# BatebitControllerShieldv0_2_0.net
KiCad netlist of a schematic drawn in EAGLE
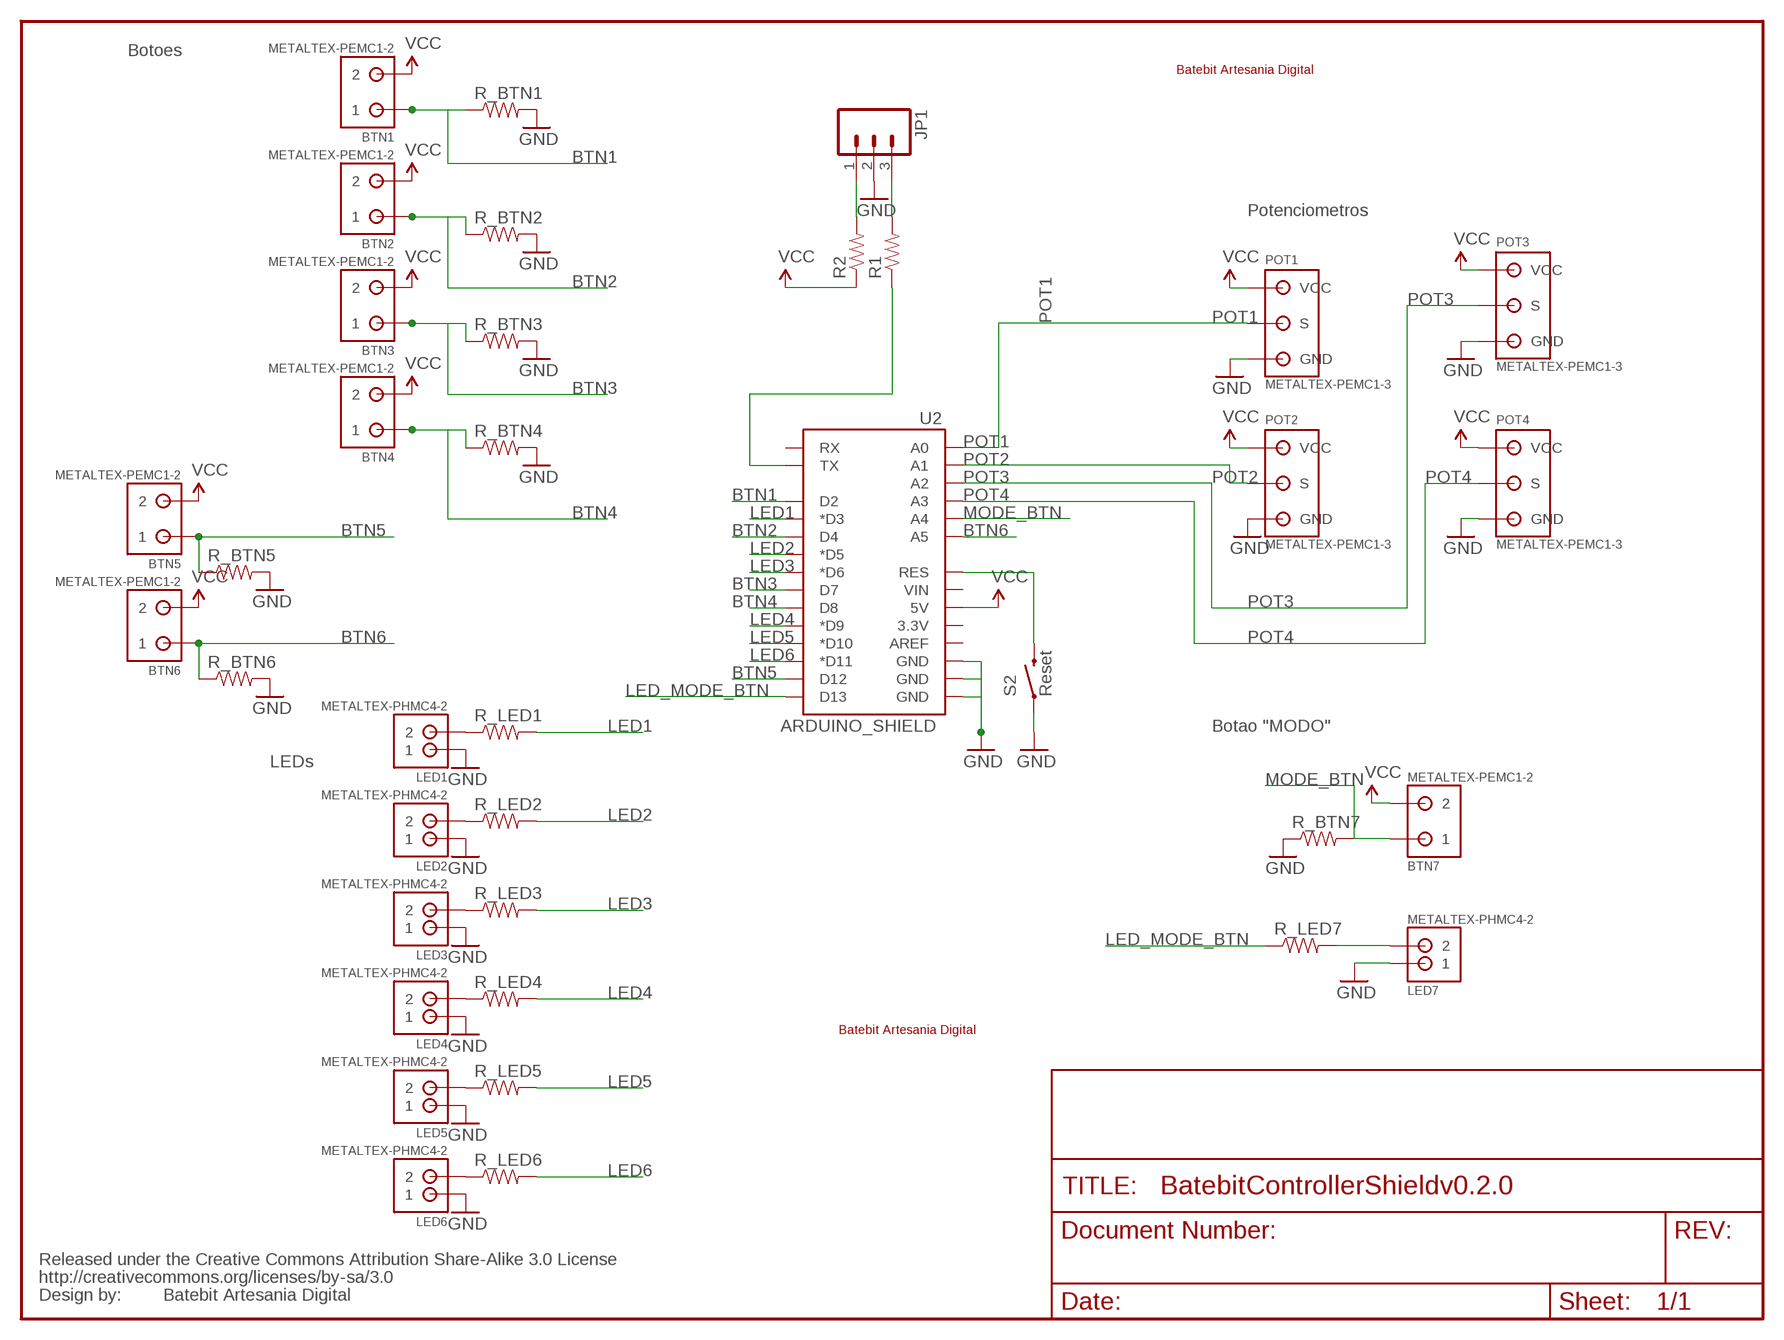
[diagram p0: schematic, sheet 1]

(export (version "E")
  (design (tool "Eeschema 10.0.6"))
  (components
    (comp (ref "BTN1")
      (value "METALTEX-PEMC1-2")
      (footprint "eagle-import:METALTEX-PEMC1-2-PACKAGE-LONG-PAD")
      (libsource (lib "eagle-import") (part "METALTEX-PEMC1-2"))
    )
    (comp (ref "BTN2")
      (value "METALTEX-PEMC1-2")
      (footprint "eagle-import:METALTEX-PEMC1-2-PACKAGE-LONG-PAD")
      (libsource (lib "eagle-import") (part "METALTEX-PEMC1-2"))
    )
    (comp (ref "BTN3")
      (value "METALTEX-PEMC1-2")
      (footprint "eagle-import:METALTEX-PEMC1-2-PACKAGE-LONG-PAD")
      (libsource (lib "eagle-import") (part "METALTEX-PEMC1-2"))
    )
    (comp (ref "BTN4")
      (value "METALTEX-PEMC1-2")
      (footprint "eagle-import:METALTEX-PEMC1-2-PACKAGE-LONG-PAD")
      (libsource (lib "eagle-import") (part "METALTEX-PEMC1-2"))
    )
    (comp (ref "BTN5")
      (value "METALTEX-PEMC1-2")
      (footprint "eagle-import:METALTEX-PEMC1-2-PACKAGE-LONG-PAD")
      (libsource (lib "eagle-import") (part "METALTEX-PEMC1-2"))
    )
    (comp (ref "BTN6")
      (value "METALTEX-PEMC1-2")
      (footprint "eagle-import:METALTEX-PEMC1-2-PACKAGE-LONG-PAD")
      (libsource (lib "eagle-import") (part "METALTEX-PEMC1-2"))
    )
    (comp (ref "BTN7")
      (value "METALTEX-PEMC1-2")
      (footprint "eagle-import:METALTEX-PEMC1-2-PACKAGE-LONG-PAD")
      (libsource (lib "eagle-import") (part "METALTEX-PEMC1-2"))
    )
    (comp (ref "JP1")
      (value "M03LONGPADS")
      (footprint "eagle-import:1X03_LONGPADS")
      (libsource (lib "eagle-import") (part "M03LONGPADS"))
    )
    (comp (ref "LED1")
      (value "METALTEX-PHMC4-2")
      (footprint "eagle-import:METALTEX-PHMC4-2-PACKAGE-LONG-PAD")
      (libsource (lib "eagle-import") (part "METALTEX-PHMC4-2"))
    )
    (comp (ref "LED2")
      (value "METALTEX-PHMC4-2")
      (footprint "eagle-import:METALTEX-PHMC4-2-PACKAGE-LONG-PAD")
      (libsource (lib "eagle-import") (part "METALTEX-PHMC4-2"))
    )
    (comp (ref "LED3")
      (value "METALTEX-PHMC4-2")
      (footprint "eagle-import:METALTEX-PHMC4-2-PACKAGE-LONG-PAD")
      (libsource (lib "eagle-import") (part "METALTEX-PHMC4-2"))
    )
    (comp (ref "LED4")
      (value "METALTEX-PHMC4-2")
      (footprint "eagle-import:METALTEX-PHMC4-2-PACKAGE-LONG-PAD")
      (libsource (lib "eagle-import") (part "METALTEX-PHMC4-2"))
    )
    (comp (ref "LED5")
      (value "METALTEX-PHMC4-2")
      (footprint "eagle-import:METALTEX-PHMC4-2-PACKAGE-LONG-PAD")
      (libsource (lib "eagle-import") (part "METALTEX-PHMC4-2"))
    )
    (comp (ref "LED6")
      (value "METALTEX-PHMC4-2")
      (footprint "eagle-import:METALTEX-PHMC4-2-PACKAGE-LONG-PAD")
      (libsource (lib "eagle-import") (part "METALTEX-PHMC4-2"))
    )
    (comp (ref "LED7")
      (value "METALTEX-PHMC4-2")
      (footprint "eagle-import:METALTEX-PHMC4-2-PACKAGE-LONG-PAD")
      (libsource (lib "eagle-import") (part "METALTEX-PHMC4-2"))
    )
    (comp (ref "POT1")
      (value "METALTEX-PEMC1-3")
      (footprint "eagle-import:METALTEX-PEMC1-3-PACKAGE-LONG-PAD")
      (libsource (lib "eagle-import") (part "METALTEX-PEMC1-3"))
    )
    (comp (ref "POT2")
      (value "METALTEX-PEMC1-3")
      (footprint "eagle-import:METALTEX-PEMC1-3-PACKAGE-LONG-PAD")
      (libsource (lib "eagle-import") (part "METALTEX-PEMC1-3"))
    )
    (comp (ref "POT3")
      (value "METALTEX-PEMC1-3")
      (footprint "eagle-import:METALTEX-PEMC1-3-PACKAGE-LONG-PAD")
      (libsource (lib "eagle-import") (part "METALTEX-PEMC1-3"))
    )
    (comp (ref "POT4")
      (value "METALTEX-PEMC1-3")
      (footprint "eagle-import:METALTEX-PEMC1-3-PACKAGE-LONG-PAD")
      (libsource (lib "eagle-import") (part "METALTEX-PEMC1-3"))
    )
    (comp (ref "R1")
      (value "RESISTOR0805-RES")
      (footprint "eagle-import:0805")
      (libsource (lib "eagle-import") (part "RESISTOR0805-RES"))
    )
    (comp (ref "R2")
      (value "RESISTOR0805-RES")
      (footprint "eagle-import:0805")
      (libsource (lib "eagle-import") (part "RESISTOR0805-RES"))
    )
    (comp (ref "R_BTN1")
      (value "RESISTOR0805-RES")
      (footprint "eagle-import:0805")
      (libsource (lib "eagle-import") (part "RESISTOR0805-RES"))
    )
    (comp (ref "R_BTN2")
      (value "RESISTOR0805-RES")
      (footprint "eagle-import:0805")
      (libsource (lib "eagle-import") (part "RESISTOR0805-RES"))
    )
    (comp (ref "R_BTN3")
      (value "RESISTOR0805-RES")
      (footprint "eagle-import:0805")
      (libsource (lib "eagle-import") (part "RESISTOR0805-RES"))
    )
    (comp (ref "R_BTN4")
      (value "RESISTOR0805-RES")
      (footprint "eagle-import:0805")
      (libsource (lib "eagle-import") (part "RESISTOR0805-RES"))
    )
    (comp (ref "R_BTN5")
      (value "RESISTOR0805-RES")
      (footprint "eagle-import:0805")
      (libsource (lib "eagle-import") (part "RESISTOR0805-RES"))
    )
    (comp (ref "R_BTN6")
      (value "RESISTOR0805-RES")
      (footprint "eagle-import:0805")
      (libsource (lib "eagle-import") (part "RESISTOR0805-RES"))
    )
    (comp (ref "R_BTN7")
      (value "RESISTOR0805-RES")
      (footprint "eagle-import:0805")
      (libsource (lib "eagle-import") (part "RESISTOR0805-RES"))
    )
    (comp (ref "R_LED1")
      (value "RESISTOR0805-RES")
      (footprint "eagle-import:0805")
      (libsource (lib "eagle-import") (part "RESISTOR0805-RES"))
    )
    (comp (ref "R_LED2")
      (value "RESISTOR0805-RES")
      (footprint "eagle-import:0805")
      (libsource (lib "eagle-import") (part "RESISTOR0805-RES"))
    )
    (comp (ref "R_LED3")
      (value "RESISTOR0805-RES")
      (footprint "eagle-import:0805")
      (libsource (lib "eagle-import") (part "RESISTOR0805-RES"))
    )
    (comp (ref "R_LED4")
      (value "RESISTOR0805-RES")
      (footprint "eagle-import:0805")
      (libsource (lib "eagle-import") (part "RESISTOR0805-RES"))
    )
    (comp (ref "R_LED5")
      (value "RESISTOR0805-RES")
      (footprint "eagle-import:0805")
      (libsource (lib "eagle-import") (part "RESISTOR0805-RES"))
    )
    (comp (ref "R_LED6")
      (value "RESISTOR0805-RES")
      (footprint "eagle-import:0805")
      (libsource (lib "eagle-import") (part "RESISTOR0805-RES"))
    )
    (comp (ref "R_LED7")
      (value "RESISTOR0805-RES")
      (footprint "eagle-import:0805")
      (libsource (lib "eagle-import") (part "RESISTOR0805-RES"))
    )
    (comp (ref "S2")
      (value "Reset")
      (footprint "eagle-import:TACTILE_SWITCH_SMD")
      (libsource (lib "eagle-import") (part "SWITCH-MOMENTARY-2SMD"))
    )
    (comp (ref "U$1")
      (value "BATEBITP")
      (footprint "eagle-import:BATEBIT_BRASAO_P")
      (libsource (lib "eagle-import") (part "BATEBITP"))
    )
    (comp (ref "U$2")
      (value "BATEBITMED")
      (footprint "eagle-import:BATEBIT_MED")
      (libsource (lib "eagle-import") (part "BATEBITMED"))
    )
    (comp (ref "U$3")
      (value "CREATIVE_COMMONS")
      (footprint "eagle-import:CREATIVE_COMMONS")
      (libsource (lib "eagle-import") (part "CREATIVE_COMMONS"))
    )
    (comp (ref "U2")
      (value "ARDUINO_SHIELD")
      (footprint "eagle-import:DUEMILANOVE_SHIELD")
      (libsource (lib "eagle-import") (part "ARDUINO_SHIELDLABEL"))
    )
  )
  (nets
    (net (code "1") (name "/BTN1") (class "Default")
      (node (ref "BTN1") (pin "1") (pinfunction "1_1") (pintype "bidirectional"))
      (node (ref "R_BTN1") (pin "1") (pinfunction "1_1") (pintype "passive"))
      (node (ref "U2") (pin "D2") (pinfunction "D2_D2") (pintype "bidirectional"))
    )
    (net (code "2") (name "/BTN2") (class "Default")
      (node (ref "BTN2") (pin "1") (pinfunction "1_1") (pintype "bidirectional"))
      (node (ref "R_BTN2") (pin "1") (pinfunction "1_1") (pintype "passive"))
      (node (ref "U2") (pin "D4") (pinfunction "D4_D4") (pintype "bidirectional"))
    )
    (net (code "3") (name "/BTN3") (class "Default")
      (node (ref "BTN3") (pin "1") (pinfunction "1_1") (pintype "bidirectional"))
      (node (ref "R_BTN3") (pin "1") (pinfunction "1_1") (pintype "passive"))
      (node (ref "U2") (pin "D7") (pinfunction "D7_D7") (pintype "bidirectional"))
    )
    (net (code "4") (name "/BTN4") (class "Default")
      (node (ref "BTN4") (pin "1") (pinfunction "1_1") (pintype "bidirectional"))
      (node (ref "R_BTN4") (pin "1") (pinfunction "1_1") (pintype "passive"))
      (node (ref "U2") (pin "D8") (pinfunction "D8_D8") (pintype "bidirectional"))
    )
    (net (code "5") (name "/BTN5") (class "Default")
      (node (ref "BTN5") (pin "1") (pinfunction "1_1") (pintype "bidirectional"))
      (node (ref "R_BTN5") (pin "1") (pinfunction "1_1") (pintype "passive"))
      (node (ref "U2") (pin "D12") (pinfunction "D12_D12") (pintype "bidirectional"))
    )
    (net (code "6") (name "/BTN6") (class "Default")
      (node (ref "BTN6") (pin "1") (pinfunction "1_1") (pintype "bidirectional"))
      (node (ref "R_BTN6") (pin "1") (pinfunction "1_1") (pintype "passive"))
      (node (ref "U2") (pin "A5") (pinfunction "A5_A5") (pintype "bidirectional"))
    )
    (net (code "7") (name "/LED1") (class "Default")
      (node (ref "R_LED1") (pin "2") (pinfunction "2_2") (pintype "passive"))
      (node (ref "U2") (pin "D3") (pinfunction "*D3_D3") (pintype "bidirectional"))
    )
    (net (code "8") (name "/LED2") (class "Default")
      (node (ref "R_LED2") (pin "2") (pinfunction "2_2") (pintype "passive"))
      (node (ref "U2") (pin "D5") (pinfunction "*D5_D5") (pintype "bidirectional"))
    )
    (net (code "9") (name "/LED3") (class "Default")
      (node (ref "R_LED3") (pin "2") (pinfunction "2_2") (pintype "passive"))
      (node (ref "U2") (pin "D6") (pinfunction "*D6_D6") (pintype "bidirectional"))
    )
    (net (code "10") (name "/LED4") (class "Default")
      (node (ref "R_LED4") (pin "2") (pinfunction "2_2") (pintype "passive"))
      (node (ref "U2") (pin "D9") (pinfunction "*D9_D9") (pintype "bidirectional"))
    )
    (net (code "11") (name "/LED5") (class "Default")
      (node (ref "R_LED5") (pin "2") (pinfunction "2_2") (pintype "passive"))
      (node (ref "U2") (pin "D10") (pinfunction "*D10_D10") (pintype "bidirectional"))
    )
    (net (code "12") (name "/LED6") (class "Default")
      (node (ref "R_LED6") (pin "2") (pinfunction "2_2") (pintype "passive"))
      (node (ref "U2") (pin "D11") (pinfunction "*D11_D11") (pintype "bidirectional"))
    )
    (net (code "13") (name "/LED_MODE_BTN") (class "Default")
      (node (ref "R_LED7") (pin "1") (pinfunction "1_1") (pintype "passive"))
      (node (ref "U2") (pin "D13") (pinfunction "D13_D13") (pintype "bidirectional"))
    )
    (net (code "14") (name "/MODE_BTN") (class "Default")
      (node (ref "BTN7") (pin "1") (pinfunction "1_1") (pintype "bidirectional"))
      (node (ref "R_BTN7") (pin "2") (pinfunction "2_2") (pintype "passive"))
      (node (ref "U2") (pin "A4") (pinfunction "A4_A4") (pintype "bidirectional"))
    )
    (net (code "15") (name "/POT1") (class "Default")
      (node (ref "POT1") (pin "2") (pinfunction "S_2") (pintype "bidirectional"))
      (node (ref "U2") (pin "A0") (pinfunction "A0_A0") (pintype "bidirectional"))
    )
    (net (code "16") (name "/POT2") (class "Default")
      (node (ref "POT2") (pin "2") (pinfunction "S_2") (pintype "bidirectional"))
      (node (ref "U2") (pin "A1") (pinfunction "A1_A1") (pintype "bidirectional"))
    )
    (net (code "17") (name "/POT3") (class "Default")
      (node (ref "POT3") (pin "2") (pinfunction "S_2") (pintype "bidirectional"))
      (node (ref "U2") (pin "A2") (pinfunction "A2_A2") (pintype "bidirectional"))
    )
    (net (code "18") (name "/POT4") (class "Default")
      (node (ref "POT4") (pin "2") (pinfunction "S_2") (pintype "bidirectional"))
      (node (ref "U2") (pin "A3") (pinfunction "A3_A3") (pintype "bidirectional"))
    )
    (net (code "19") (name "GND") (class "Default")
      (node (ref "JP1") (pin "2") (pinfunction "2_2") (pintype "passive"))
      (node (ref "LED1") (pin "P1") (pinfunction "1_P1") (pintype "bidirectional"))
      (node (ref "LED2") (pin "P1") (pinfunction "1_P1") (pintype "bidirectional"))
      (node (ref "LED3") (pin "P1") (pinfunction "1_P1") (pintype "bidirectional"))
      (node (ref "LED4") (pin "P1") (pinfunction "1_P1") (pintype "bidirectional"))
      (node (ref "LED5") (pin "P1") (pinfunction "1_P1") (pintype "bidirectional"))
      (node (ref "LED6") (pin "P1") (pinfunction "1_P1") (pintype "bidirectional"))
      (node (ref "LED7") (pin "P1") (pinfunction "1_P1") (pintype "bidirectional"))
      (node (ref "POT1") (pin "1") (pinfunction "GND_1") (pintype "bidirectional"))
      (node (ref "POT2") (pin "1") (pinfunction "GND_1") (pintype "bidirectional"))
      (node (ref "POT3") (pin "1") (pinfunction "GND_1") (pintype "bidirectional"))
      (node (ref "POT4") (pin "1") (pinfunction "GND_1") (pintype "bidirectional"))
      (node (ref "R_BTN1") (pin "2") (pinfunction "2_2") (pintype "passive"))
      (node (ref "R_BTN2") (pin "2") (pinfunction "2_2") (pintype "passive"))
      (node (ref "R_BTN3") (pin "2") (pinfunction "2_2") (pintype "passive"))
      (node (ref "R_BTN4") (pin "2") (pinfunction "2_2") (pintype "passive"))
      (node (ref "R_BTN5") (pin "2") (pinfunction "2_2") (pintype "passive"))
      (node (ref "R_BTN6") (pin "2") (pinfunction "2_2") (pintype "passive"))
      (node (ref "R_BTN7") (pin "1") (pinfunction "1_1") (pintype "passive"))
      (node (ref "S2") (pin "1") (pinfunction "1_1") (pintype "passive"))
      (node (ref "U2") (pin "GND@0") (pinfunction "GND_GND@0") (pintype "bidirectional"))
      (node (ref "U2") (pin "GND@1") (pinfunction "GND_GND@1") (pintype "bidirectional"))
      (node (ref "U2") (pin "GND@2") (pinfunction "GND_GND@2") (pintype "bidirectional"))
    )
    (net (code "20") (name "Net-(JP1-Pad1)") (class "Default")
      (node (ref "JP1") (pin "1") (pinfunction "1_1") (pintype "passive"))
      (node (ref "R2") (pin "2") (pinfunction "2_2") (pintype "passive"))
    )
    (net (code "21") (name "Net-(JP1-Pad3)") (class "Default")
      (node (ref "JP1") (pin "3") (pinfunction "3_3") (pintype "passive"))
      (node (ref "R1") (pin "2") (pinfunction "2_2") (pintype "passive"))
    )
    (net (code "22") (name "Net-(LED1-2)") (class "Default")
      (node (ref "LED1") (pin "P2") (pinfunction "2_P2") (pintype "bidirectional"))
      (node (ref "R_LED1") (pin "1") (pinfunction "1_1") (pintype "passive"))
    )
    (net (code "23") (name "Net-(LED2-2)") (class "Default")
      (node (ref "LED2") (pin "P2") (pinfunction "2_P2") (pintype "bidirectional"))
      (node (ref "R_LED2") (pin "1") (pinfunction "1_1") (pintype "passive"))
    )
    (net (code "24") (name "Net-(LED3-2)") (class "Default")
      (node (ref "LED3") (pin "P2") (pinfunction "2_P2") (pintype "bidirectional"))
      (node (ref "R_LED3") (pin "1") (pinfunction "1_1") (pintype "passive"))
    )
    (net (code "25") (name "Net-(LED4-2)") (class "Default")
      (node (ref "LED4") (pin "P2") (pinfunction "2_P2") (pintype "bidirectional"))
      (node (ref "R_LED4") (pin "1") (pinfunction "1_1") (pintype "passive"))
    )
    (net (code "26") (name "Net-(LED5-2)") (class "Default")
      (node (ref "LED5") (pin "P2") (pinfunction "2_P2") (pintype "bidirectional"))
      (node (ref "R_LED5") (pin "1") (pinfunction "1_1") (pintype "passive"))
    )
    (net (code "27") (name "Net-(LED6-2)") (class "Default")
      (node (ref "LED6") (pin "P2") (pinfunction "2_P2") (pintype "bidirectional"))
      (node (ref "R_LED6") (pin "1") (pinfunction "1_1") (pintype "passive"))
    )
    (net (code "28") (name "Net-(LED7-2)") (class "Default")
      (node (ref "LED7") (pin "P2") (pinfunction "2_P2") (pintype "bidirectional"))
      (node (ref "R_LED7") (pin "2") (pinfunction "2_2") (pintype "passive"))
    )
    (net (code "29") (name "Net-(R1-Pad1)") (class "Default")
      (node (ref "R1") (pin "1") (pinfunction "1_1") (pintype "passive"))
      (node (ref "U2") (pin "TX") (pinfunction "TX_TX") (pintype "bidirectional"))
    )
    (net (code "30") (name "Net-(S2-2)") (class "Default")
      (node (ref "S2") (pin "3") (pinfunction "2_3") (pintype "passive"))
      (node (ref "U2") (pin "RES") (pinfunction "RES_RES") (pintype "bidirectional"))
    )
    (net (code "31") (name "VCC") (class "Default")
      (node (ref "BTN1") (pin "2") (pinfunction "2_2") (pintype "bidirectional"))
      (node (ref "BTN2") (pin "2") (pinfunction "2_2") (pintype "bidirectional"))
      (node (ref "BTN3") (pin "2") (pinfunction "2_2") (pintype "bidirectional"))
      (node (ref "BTN4") (pin "2") (pinfunction "2_2") (pintype "bidirectional"))
      (node (ref "BTN5") (pin "2") (pinfunction "2_2") (pintype "bidirectional"))
      (node (ref "BTN6") (pin "2") (pinfunction "2_2") (pintype "bidirectional"))
      (node (ref "BTN7") (pin "2") (pinfunction "2_2") (pintype "bidirectional"))
      (node (ref "POT1") (pin "3") (pinfunction "VCC_3") (pintype "bidirectional"))
      (node (ref "POT2") (pin "3") (pinfunction "VCC_3") (pintype "bidirectional"))
      (node (ref "POT3") (pin "3") (pinfunction "VCC_3") (pintype "bidirectional"))
      (node (ref "POT4") (pin "3") (pinfunction "VCC_3") (pintype "bidirectional"))
      (node (ref "R2") (pin "1") (pinfunction "1_1") (pintype "passive"))
      (node (ref "U2") (pin "5V") (pinfunction "5V_5V") (pintype "bidirectional"))
    )
    (net (code "32") (name "unconnected-(U2-Pad3.3V)") (class "Default")
      (node (ref "U2") (pin "3.3V") (pinfunction "3.3V_3.3V") (pintype "bidirectional"))
    )
    (net (code "33") (name "unconnected-(U2-PadAREF)") (class "Default")
      (node (ref "U2") (pin "AREF") (pinfunction "AREF_AREF") (pintype "bidirectional"))
    )
    (net (code "34") (name "unconnected-(U2-PadRX)") (class "Default")
      (node (ref "U2") (pin "RX") (pinfunction "RX_RX") (pintype "bidirectional"))
    )
    (net (code "35") (name "unconnected-(U2-PadVIN)") (class "Default")
      (node (ref "U2") (pin "VIN") (pinfunction "VIN_VIN") (pintype "bidirectional"))
    )
  )
)
